# 1.net
KiCad netlist of a schematic drawn in Altium Designer
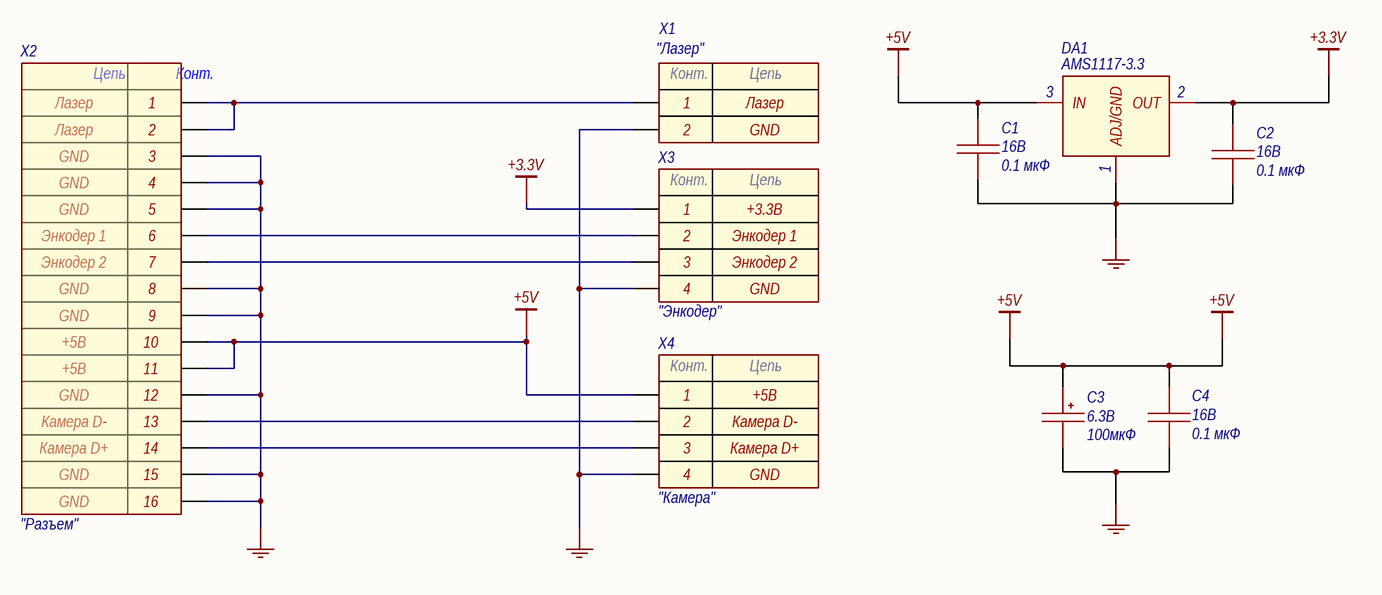
[diagram p0: Лист 1.SchDoc]

(export (version "E")
  (design (tool "Eeschema 10.0.6"))
  (components
    (comp (ref "C1")
      (value "0.1 мкФ")
      (footprint "StandardCase:CAP: 0805")
      (fields
        (field (name "MANUFACTURER") "Yageo")
        (field (name "PARTNUMBER") "CC0805KRX7R7BB104")
        (field (name "VALUEMANUFACTURERPARTNUMBER") "Ceramic capacitor, 0.1 мкФ, X7R, ±10%, 16В, 0805, -55...+125°C")
        (field (name "VOLTAGE") "16В")
      )
      (libsource (lib "Capacitor") (part "Ceramic_0805"))
    )
    (comp (ref "C2")
      (value "0.1 мкФ")
      (footprint "StandardCase:CAP: 0805")
      (fields
        (field (name "MANUFACTURER") "Yageo")
        (field (name "PARTNUMBER") "CC0805KRX7R7BB104")
        (field (name "VALUEMANUFACTURERPARTNUMBER") "Ceramic capacitor, 0.1 мкФ, X7R, ±10%, 16В, 0805, -55...+125°C")
        (field (name "VOLTAGE") "16В")
      )
      (libsource (lib "Capacitor") (part "Ceramic_0805"))
    )
    (comp (ref "C3")
      (value "100мкФ")
      (footprint "StandardCase:CAP: TANTAL-A")
      (fields
        (field (name "MANUFACTURER") "AVX")
        (field (name "PARTNUMBER") "F930J107KAAAJ6")
        (field (name "VALUEMANUFACTURERPARTNUMBER") "Tantalum capacitor, 100мкФ, 6.3В, ±10%, 2Ohm, case A (3216), -55...+125°C")
        (field (name "VOLTAGE") "6.3В")
      )
      (libsource (lib "Capacitor") (part "Tantal_A"))
    )
    (comp (ref "C4")
      (value "0.1 мкФ")
      (footprint "StandardCase:CAP: 0805")
      (fields
        (field (name "MANUFACTURER") "Yageo")
        (field (name "PARTNUMBER") "CC0805KRX7R7BB104")
        (field (name "VALUEMANUFACTURERPARTNUMBER") "Ceramic capacitor, 0.1 мкФ, X7R, ±10%, 16В, 0805, -55...+125°C")
        (field (name "VOLTAGE") "16В")
      )
      (libsource (lib "Capacitor") (part "Ceramic_0805"))
    )
    (comp (ref "DA1")
      (value "AMS1117-3.3")
      (footprint "StandardCase:SOT223 AMS1117")
      (libsource (lib "Linear Voltage Regulators") (part "AMS1117"))
    )
    (comp (ref "X1")
      (value "~")
      (footprint "CustomCase:CON: CWF-2")
      (fields
        (field (name "MANUFACTURER") "Connfly")
        (field (name "VALUEMANUFACTURERPARTNUMBER") "Connector, 2pin, 2.54mm, 250VAC, 3A")
        (field (name "PARTNUMBER") "CWF-2R")
        (field (name "COMMENTTEXT") "\"Лазер\"")
      )
      (libsource (lib "Connector") (part "CWF-2R(CWF-2)"))
    )
    (comp (ref "X2")
      (value "\"Разъем\"")
      (footprint "CustomCase:CON: 52207-1633, FFC / FPC")
      (libsource (lib "Connector") (part "52207-1633, FFC / FPC"))
    )
    (comp (ref "X3")
      (value "~")
      (footprint "CustomCase:CON: CWF-4")
      (fields
        (field (name "MANUFACTURER") "Connfly")
        (field (name "VALUEMANUFACTURERPARTNUMBER") "Connector, 4pin, 2.54mm, 250VAC, 3A")
        (field (name "PARTNUMBER") "CWF-4R")
        (field (name "COMMENTTEXT") "\"Энкодер\"")
      )
      (libsource (lib "Connector") (part "CWF-4R(CWF-4)"))
    )
    (comp (ref "X4")
      (value "~")
      (footprint "CustomCase:CON: CWF-4")
      (fields
        (field (name "MANUFACTURER") "Connfly")
        (field (name "VALUEMANUFACTURERPARTNUMBER") "Connector, 4pin, 2.54mm, 250VAC, 3A")
        (field (name "PARTNUMBER") "CWF-4R")
        (field (name "COMMENTTEXT") "\"Камера\"")
      )
      (libsource (lib "Connector") (part "CWF-4R(CWF-4)"))
    )
  )
  (nets
    (net (code "1") (name "+3.3V") (class "Default")
      (node (ref "C2") (pin "2") (pinfunction "2_2") (pintype "power_in"))
      (node (ref "DA1") (pin "2") (pinfunction "OUT_2") (pintype "passive"))
      (node (ref "X3") (pin "1") (pinfunction "1_1") (pintype "passive"))
    )
    (net (code "2") (name "+5V") (class "Default")
      (node (ref "C1") (pin "2") (pinfunction "2_2") (pintype "power_in"))
      (node (ref "C3") (pin "1") (pinfunction "1_1") (pintype "power_in"))
      (node (ref "C4") (pin "2") (pinfunction "2_2") (pintype "power_in"))
      (node (ref "DA1") (pin "3") (pinfunction "IN_3") (pintype "passive"))
      (node (ref "X2") (pin "10") (pinfunction "10_10") (pintype "power_in"))
      (node (ref "X2") (pin "11") (pinfunction "11_11") (pintype "power_in"))
      (node (ref "X4") (pin "1") (pinfunction "1_1") (pintype "passive"))
    )
    (net (code "3") (name "GND") (class "Default")
      (node (ref "C1") (pin "1") (pinfunction "1_1") (pintype "power_in"))
      (node (ref "C2") (pin "1") (pinfunction "1_1") (pintype "power_in"))
      (node (ref "C3") (pin "2") (pinfunction "2_2") (pintype "power_in"))
      (node (ref "C4") (pin "1") (pinfunction "1_1") (pintype "power_in"))
      (node (ref "DA1") (pin "1") (pinfunction "ADJ/GND_1") (pintype "passive"))
      (node (ref "X1") (pin "2") (pinfunction "2_2") (pintype "passive"))
      (node (ref "X2") (pin "12") (pinfunction "12_12") (pintype "power_in"))
      (node (ref "X2") (pin "15") (pinfunction "15_15") (pintype "power_in"))
      (node (ref "X2") (pin "16") (pinfunction "16_16") (pintype "power_in"))
      (node (ref "X2") (pin "3") (pinfunction "3_3") (pintype "power_in"))
      (node (ref "X2") (pin "4") (pinfunction "4_4") (pintype "power_in"))
      (node (ref "X2") (pin "5") (pinfunction "5_5") (pintype "power_in"))
      (node (ref "X2") (pin "8") (pinfunction "8_8") (pintype "power_in"))
      (node (ref "X2") (pin "9") (pinfunction "9_9") (pintype "power_in"))
      (node (ref "X3") (pin "4") (pinfunction "4_4") (pintype "power_in"))
      (node (ref "X4") (pin "4") (pinfunction "4_4") (pintype "power_in"))
    )
    (net (code "4") (name "Net-(X1-Pad1)") (class "Default")
      (node (ref "X1") (pin "1") (pinfunction "1_1") (pintype "passive"))
      (node (ref "X2") (pin "1") (pinfunction "1_1") (pintype "passive"))
      (node (ref "X2") (pin "2") (pinfunction "2_2") (pintype "passive"))
    )
    (net (code "5") (name "Net-(X2-Pad6)") (class "Default")
      (node (ref "X2") (pin "6") (pinfunction "6_6") (pintype "power_in"))
      (node (ref "X3") (pin "2") (pinfunction "2_2") (pintype "passive"))
    )
    (net (code "6") (name "Net-(X2-Pad7)") (class "Default")
      (node (ref "X2") (pin "7") (pinfunction "7_7") (pintype "power_in"))
      (node (ref "X3") (pin "3") (pinfunction "3_3") (pintype "power_in"))
    )
    (net (code "7") (name "Net-(X2-Pad13)") (class "Default")
      (node (ref "X2") (pin "13") (pinfunction "13_13") (pintype "power_in"))
      (node (ref "X4") (pin "2") (pinfunction "2_2") (pintype "passive"))
    )
    (net (code "8") (name "Net-(X2-Pad14)") (class "Default")
      (node (ref "X2") (pin "14") (pinfunction "14_14") (pintype "power_in"))
      (node (ref "X4") (pin "3") (pinfunction "3_3") (pintype "power_in"))
    )
  )
)
